# Sheet1.net
KiCad netlist of a schematic drawn in Altium Designer
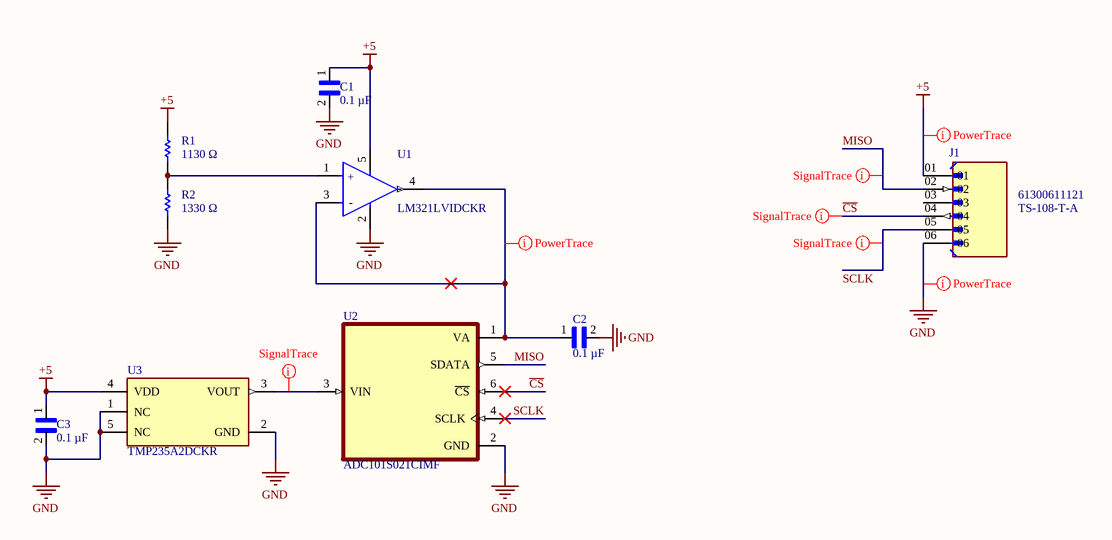
[diagram p0: Sheet1.SchDoc]

(export (version "E")
  (design (tool "Eeschema 10.0.6"))
  (components
    (comp (ref "C1")
      (value "0.1 µF")
      (footprint "PcbLib1:CAPC1005X55N")
      (description "0.1ÂµF -20%, +80% 16V Ceramic Capacitor Y5V (F) 0402 (1005 Metric)")
      (fields (field (name "MP") "CC0402ZRY5V7BB104") (field (name "MF") "Yageo"))
      (libsource (lib "") (part "CC0402ZRY5V7BB104_1"))
    )
    (comp (ref "C2")
      (value "0.1 µF")
      (footprint "PcbLib1:CAPC1005X55N")
      (description "0.1ÂµF -20%, +80% 16V Ceramic Capacitor Y5V (F) 0402 (1005 Metric)")
      (fields (field (name "MP") "CC0402ZRY5V7BB104") (field (name "MF") "Yageo"))
      (libsource (lib "Schlib1") (part "CC0402ZRY5V7BB104"))
    )
    (comp (ref "C3")
      (value "0.1 µF")
      (footprint "PcbLib1:CAPC1005X55N")
      (description "0.1ÂµF -20%, +80% 16V Ceramic Capacitor Y5V (F) 0402 (1005 Metric)")
      (fields (field (name "MP") "CC0402ZRY5V7BB104") (field (name "MF") "Yageo"))
      (libsource (lib "") (part "CC0402ZRY5V7BB104_1"))
    )
    (comp (ref "J1")
      (value "61300611121")
      (footprint "CON-WURTH_61300611121")
      (fields
        (field (name "MF") "Wurth Electronics")
        (field (name "MANUFACTURER") "Samtec")
        (field (name "MANUFACTURER PART NUMBER") "TS-108-T-A")
        (field (name "SUPPLIER PART NUMBER 1") "TS-108-T-A")
      )
      (libsource (lib "Schlib1") (part "61300611121"))
    )
    (comp (ref "R1")
      (value "1130 Ω")
      (footprint "RESC1005X40X25ML05T10")
      (fields (field (name "MANUFACTURER") "Yageo") (field (name "PART NUMBER") "RC0402FR-071K13L"))
      (libsource (lib "Schlib1") (part "CMP-1011-00515-2"))
    )
    (comp (ref "R2")
      (value "1330 Ω")
      (footprint "RESC1005X40X25ML05T10")
      (fields (field (name "MANUFACTURER") "Yageo") (field (name "PART NUMBER") "RC0402FR-071K33L"))
      (libsource (lib "Schlib1") (part "CMP-2002-07457-1"))
    )
    (comp (ref "U1")
      (value "LM321LVIDCKR")
      (footprint "FP-DCK0005A-IPC_A")
      (description "IC OPAMP GP 1 CIRCUIT SC70-5")
      (libsource (lib "Schlib1") (part "CMP-04895-000147-1"))
    )
    (comp (ref "U2")
      (value "ADC101S021CIMF")
      (footprint "ADC-SOT95P280X145-6N")
      (fields
        (field (name "MF") "{'manufacturer': u'Texas Instruments'}")
        (field (name "MP") "ADC101S021CIMFX/NOPB")
      )
      (libsource (lib "Schlib1") (part "ADC101S021CIMF"))
    )
    (comp (ref "U3")
      (value "TMP235A2DCKR")
      (footprint "TMP-FP-DCK0005A-IPC_B")
      (description "SENSOR ANALOG -40C-150C SC70-5")
      (libsource (lib "Schlib1") (part "CMP-04948-000100-1"))
    )
  )
  (nets
    (net (code "1") (name "+5") (class "Default")
      (node (ref "C1") (pin "1") (pinfunction "1_1") (pintype "passive"))
      (node (ref "C3") (pin "1") (pinfunction "1_1") (pintype "passive"))
      (node (ref "J1") (pin "01") (pinfunction "01_01") (pintype "power_in"))
      (node (ref "R1") (pin "2") (pinfunction "2_2") (pintype "passive"))
      (node (ref "U1") (pin "5") (pinfunction "V+_5") (pintype "power_in"))
      (node (ref "U3") (pin "4") (pinfunction "VDD_4") (pintype "power_in"))
    )
    (net (code "2") (name "/MISO") (class "Default")
      (node (ref "J1") (pin "02") (pinfunction "02_02") (pintype "input"))
      (node (ref "U2") (pin "5") (pinfunction "SDATA_5") (pintype "output"))
    )
    (net (code "3") (name "/SCLK") (class "Default")
      (node (ref "J1") (pin "05") (pinfunction "05_05") (pintype "passive"))
      (node (ref "U2") (pin "4") (pinfunction "SCLK_4") (pintype "input"))
    )
    (net (code "4") (name "/~{CS}") (class "Default")
      (node (ref "J1") (pin "04") (pinfunction "04_04") (pintype "output"))
      (node (ref "U2") (pin "6") (pinfunction "~{CS}_6") (pintype "input"))
    )
    (net (code "5") (name "GND") (class "Default")
      (node (ref "C1") (pin "2") (pinfunction "2_2") (pintype "passive"))
      (node (ref "C2") (pin "2") (pinfunction "2_2") (pintype "passive"))
      (node (ref "C3") (pin "2") (pinfunction "2_2") (pintype "passive"))
      (node (ref "J1") (pin "06") (pinfunction "06_06") (pintype "power_in"))
      (node (ref "R2") (pin "2") (pinfunction "2_2") (pintype "passive"))
      (node (ref "U1") (pin "2") (pinfunction "V-_2") (pintype "power_in"))
      (node (ref "U2") (pin "2") (pinfunction "GND_2") (pintype "power_in"))
      (node (ref "U3") (pin "1") (pinfunction "NC_1") (pintype "passive"))
      (node (ref "U3") (pin "2") (pinfunction "GND_2") (pintype "power_in"))
      (node (ref "U3") (pin "5") (pinfunction "NC_5") (pintype "passive"))
    )
    (net (code "6") (name "Net-(U1-IN+)") (class "Default")
      (node (ref "R1") (pin "1") (pinfunction "1_1") (pintype "passive"))
      (node (ref "R2") (pin "1") (pinfunction "1_1") (pintype "passive"))
      (node (ref "U1") (pin "1") (pinfunction "IN+_1") (pintype "tri_state"))
    )
    (net (code "7") (name "Net-(U1-IN-)") (class "Default")
      (node (ref "C2") (pin "1") (pinfunction "1_1") (pintype "passive"))
      (node (ref "U1") (pin "3") (pinfunction "IN-_3") (pintype "tri_state"))
      (node (ref "U1") (pin "4") (pinfunction "OUT_4") (pintype "output"))
      (node (ref "U2") (pin "1") (pinfunction "VA_1") (pintype "power_in"))
    )
    (net (code "8") (name "Net-(U2-VIN)") (class "Default")
      (node (ref "U2") (pin "3") (pinfunction "VIN_3") (pintype "input"))
      (node (ref "U3") (pin "3") (pinfunction "VOUT_3") (pintype "output"))
    )
    (net (code "9") (name "unconnected-(J1-Pad03)") (class "Default")
      (node (ref "J1") (pin "03") (pinfunction "03_03") (pintype "passive"))
    )
  )
)
